# temp-pres.net
KiCad netlist of a schematic drawn in EAGLE
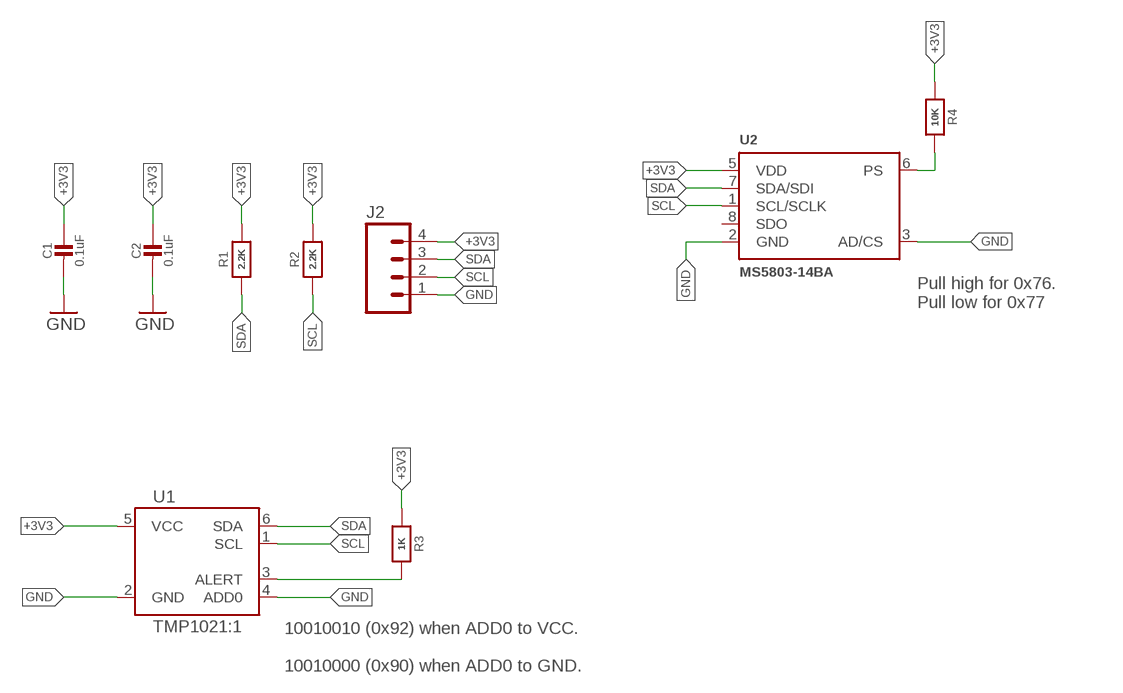
[diagram p0: schematic, sheet 1]

(export (version "E")
  (design (tool "Eeschema 10.0.6"))
  (components
    (comp (ref "C1")
      (value "0.1uF")
      (footprint "eagle-import:0805-NO")
      (libsource (lib "eagle-import") (part "CAP_CERAMIC0805-NOOUTLINE"))
    )
    (comp (ref "C2")
      (value "0.1uF")
      (footprint "eagle-import:0805-NO")
      (libsource (lib "eagle-import") (part "CAP_CERAMIC0805-NOOUTLINE"))
    )
    (comp (ref "J2")
      (value "M04NO_SILK_ALL_ROUND")
      (footprint "eagle-import:1X04_NO_SILK_ALL_ROUND")
      (libsource (lib "eagle-import") (part "M04NO_SILK_ALL_ROUND"))
    )
    (comp (ref "R1")
      (value "2.2K")
      (footprint "eagle-import:_0805MP")
      (libsource (lib "eagle-import") (part "RESISTOR_0805MP"))
    )
    (comp (ref "R2")
      (value "2.2K")
      (footprint "eagle-import:_0805MP")
      (libsource (lib "eagle-import") (part "RESISTOR_0805MP"))
    )
    (comp (ref "R3")
      (value "1K")
      (footprint "eagle-import:_0805MP")
      (libsource (lib "eagle-import") (part "RESISTOR_0805MP"))
    )
    (comp (ref "R4")
      (value "10K")
      (footprint "eagle-import:_0805MP")
      (libsource (lib "eagle-import") (part "RESISTOR_0805MP"))
    )
    (comp (ref "U1")
      (value "TMP1021:1")
      (footprint "eagle-import:SOT563-2")
      (libsource (lib "eagle-import") (part "TMP1021{colon}1"))
    )
    (comp (ref "U2")
      (value "MS5803-14BA")
      (footprint "eagle-import:MS5803")
      (libsource (lib "eagle-import") (part "MS5803-14BA"))
    )
  )
  (nets
    (net (code "1") (name "+3V3") (class "Default")
      (node (ref "C1") (pin "1") (pinfunction "1_1") (pintype "passive"))
      (node (ref "C2") (pin "1") (pinfunction "1_1") (pintype "passive"))
      (node (ref "J2") (pin "4") (pinfunction "4_4") (pintype "passive"))
      (node (ref "R1") (pin "2") (pinfunction "2_2") (pintype "passive"))
      (node (ref "R2") (pin "2") (pinfunction "2_2") (pintype "passive"))
      (node (ref "R3") (pin "1") (pinfunction "1_1") (pintype "passive"))
      (node (ref "R4") (pin "1") (pinfunction "1_1") (pintype "passive"))
      (node (ref "U1") (pin "5") (pinfunction "VCC_5") (pintype "bidirectional"))
      (node (ref "U2") (pin "5") (pinfunction "VDD_5") (pintype "bidirectional"))
    )
    (net (code "2") (name "GND") (class "Default")
      (node (ref "C1") (pin "2") (pinfunction "2_2") (pintype "passive"))
      (node (ref "C2") (pin "2") (pinfunction "2_2") (pintype "passive"))
      (node (ref "J2") (pin "1") (pinfunction "1_1") (pintype "passive"))
      (node (ref "U1") (pin "2") (pinfunction "GND_2") (pintype "bidirectional"))
      (node (ref "U1") (pin "4") (pinfunction "ADD0_4") (pintype "bidirectional"))
      (node (ref "U2") (pin "2") (pinfunction "GND_2") (pintype "bidirectional"))
      (node (ref "U2") (pin "3") (pinfunction "AD/CS_3") (pintype "bidirectional"))
    )
    (net (code "3") (name "Net-(U1-ALERT)") (class "Default")
      (node (ref "R3") (pin "2") (pinfunction "2_2") (pintype "passive"))
      (node (ref "U1") (pin "3") (pinfunction "ALERT_3") (pintype "bidirectional"))
    )
    (net (code "4") (name "Net-(U2-PS)") (class "Default")
      (node (ref "R4") (pin "2") (pinfunction "2_2") (pintype "passive"))
      (node (ref "U2") (pin "6") (pinfunction "PS_6") (pintype "bidirectional"))
    )
    (net (code "5") (name "SCL") (class "Default")
      (node (ref "J2") (pin "2") (pinfunction "2_2") (pintype "passive"))
      (node (ref "R2") (pin "1") (pinfunction "1_1") (pintype "passive"))
      (node (ref "U1") (pin "1") (pinfunction "SCL_1") (pintype "bidirectional"))
      (node (ref "U2") (pin "1") (pinfunction "SCL/SCLK_1") (pintype "bidirectional"))
    )
    (net (code "6") (name "SDA") (class "Default")
      (node (ref "J2") (pin "3") (pinfunction "3_3") (pintype "passive"))
      (node (ref "R1") (pin "1") (pinfunction "1_1") (pintype "passive"))
      (node (ref "U1") (pin "6") (pinfunction "SDA_6") (pintype "bidirectional"))
      (node (ref "U2") (pin "7") (pinfunction "SDA/SDI_7") (pintype "bidirectional"))
    )
    (net (code "7") (name "unconnected-(U2-SDO-Pad8)") (class "Default")
      (node (ref "U2") (pin "8") (pinfunction "SDO_8") (pintype "bidirectional"))
    )
  )
)
